# Adafruit_Ultimate_GPS_USB-C.net
KiCad netlist of a schematic drawn in EAGLE
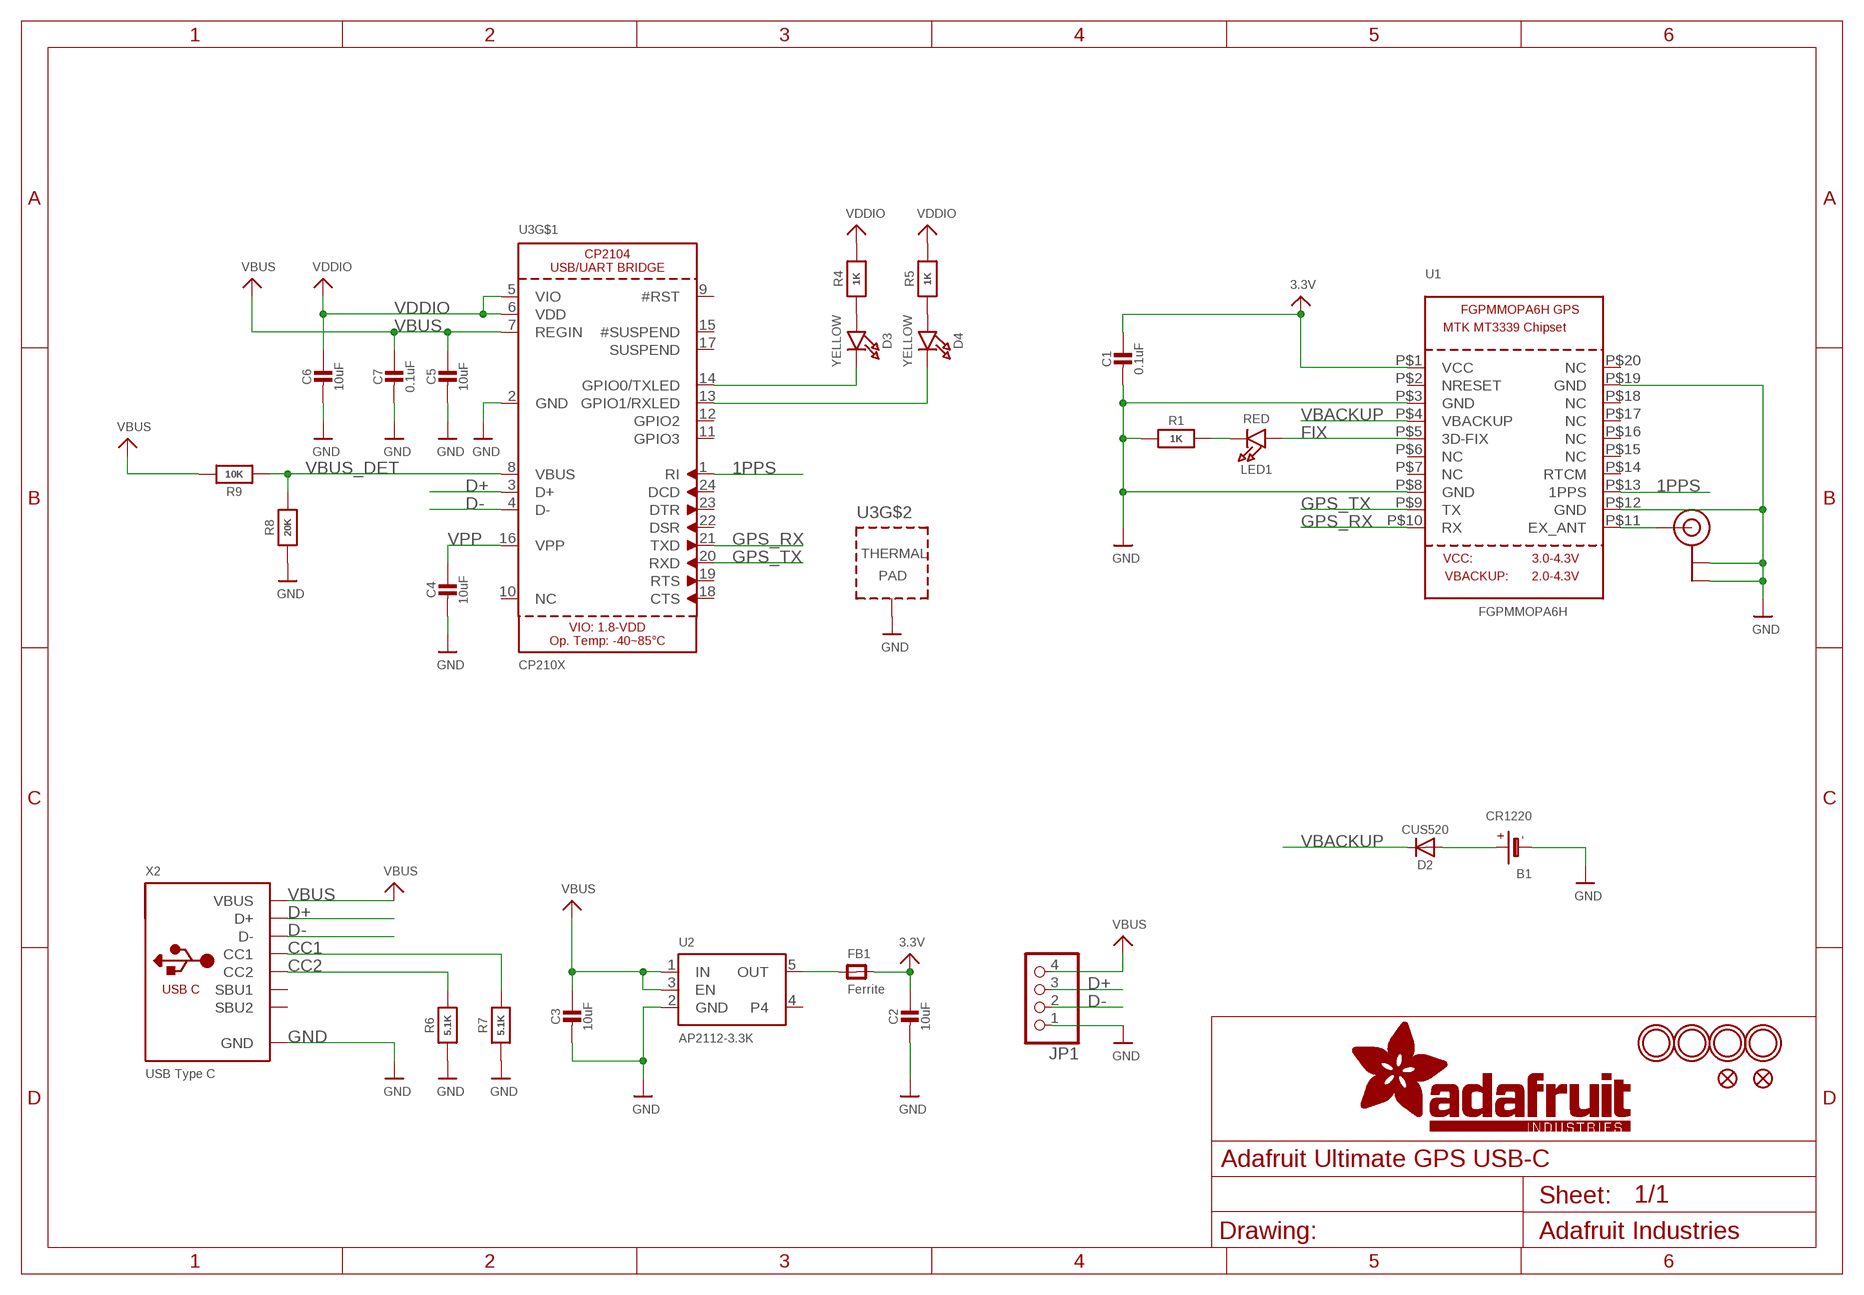
[diagram p0: schematic, sheet 1]

(export (version "E")
  (design (tool "Eeschema 10.0.6"))
  (components
    (comp (ref "B1")
      (value "CR1220")
      (footprint "eagle-import:CR1220")
      (libsource (lib "eagle-import") (part "BATTERYCR1220_SMT"))
    )
    (comp (ref "C1")
      (value "0.1uF")
      (footprint "eagle-import:0603-NO")
      (libsource (lib "eagle-import") (part "CAP_CERAMIC0603_NO"))
    )
    (comp (ref "C2")
      (value "10uF")
      (footprint "eagle-import:0805-NO")
      (libsource (lib "eagle-import") (part "CAP_CERAMIC0805-NOOUTLINE"))
    )
    (comp (ref "C3")
      (value "10uF")
      (footprint "eagle-import:0805-NO")
      (libsource (lib "eagle-import") (part "CAP_CERAMIC0805-NOOUTLINE"))
    )
    (comp (ref "C4")
      (value "10uF")
      (footprint "eagle-import:0805-NO")
      (libsource (lib "eagle-import") (part "CAP_CERAMIC0805-NOOUTLINE"))
    )
    (comp (ref "C5")
      (value "10uF")
      (footprint "eagle-import:0805-NO")
      (libsource (lib "eagle-import") (part "CAP_CERAMIC0805-NOOUTLINE"))
    )
    (comp (ref "C6")
      (value "10uF")
      (footprint "eagle-import:0805-NO")
      (libsource (lib "eagle-import") (part "CAP_CERAMIC0805-NOOUTLINE"))
    )
    (comp (ref "C7")
      (value "0.1uF")
      (footprint "eagle-import:0603-NO")
      (libsource (lib "eagle-import") (part "CAP_CERAMIC0603_NO"))
    )
    (comp (ref "D2")
      (value "CUS520")
      (footprint "eagle-import:SOD-323")
      (libsource (lib "eagle-import") (part "DIODESOD-323"))
    )
    (comp (ref "D3")
      (value "YELLOW")
      (footprint "eagle-import:CHIPLED_0805_NOOUTLINE")
      (libsource (lib "eagle-import") (part "LED0805_NOOUTLINE"))
    )
    (comp (ref "D4")
      (value "YELLOW")
      (footprint "eagle-import:CHIPLED_0805_NOOUTLINE")
      (libsource (lib "eagle-import") (part "LED0805_NOOUTLINE"))
    )
    (comp (ref "FB1")
      (value "Ferrite")
      (footprint "eagle-import:0805-NO")
      (libsource (lib "eagle-import") (part "FERRITE-0805NO"))
    )
    (comp (ref "FID1")
      (value "FIDUCIAL_1MM")
      (footprint "eagle-import:FIDUCIAL_1MM")
      (libsource (lib "eagle-import") (part "FIDUCIAL_1MM"))
    )
    (comp (ref "FID2")
      (value "FIDUCIAL_1MM")
      (footprint "eagle-import:FIDUCIAL_1MM")
      (libsource (lib "eagle-import") (part "FIDUCIAL_1MM"))
    )
    (comp (ref "JP1")
      (value "HEADER-1X4ROUND")
      (footprint "eagle-import:1X04_ROUND")
      (libsource (lib "eagle-import") (part "HEADER-1X4ROUND"))
    )
    (comp (ref "LED1")
      (value "RED")
      (footprint "eagle-import:CHIPLED_0805_NOOUTLINE")
      (libsource (lib "eagle-import") (part "LED0805_NOOUTLINE"))
    )
    (comp (ref "R1")
      (value "1K")
      (footprint "eagle-import:0603-NO")
      (libsource (lib "eagle-import") (part "RESISTOR_0603_NOOUT"))
    )
    (comp (ref "R4")
      (value "1K")
      (footprint "eagle-import:0603-NO")
      (libsource (lib "eagle-import") (part "RESISTOR_0603_NOOUT"))
    )
    (comp (ref "R5")
      (value "1K")
      (footprint "eagle-import:0603-NO")
      (libsource (lib "eagle-import") (part "RESISTOR_0603_NOOUT"))
    )
    (comp (ref "R6")
      (value "5.1K")
      (footprint "eagle-import:0603-NO")
      (libsource (lib "eagle-import") (part "RESISTOR_0603_NOOUT"))
    )
    (comp (ref "R7")
      (value "5.1K")
      (footprint "eagle-import:0603-NO")
      (libsource (lib "eagle-import") (part "RESISTOR_0603_NOOUT"))
    )
    (comp (ref "R8")
      (value "20K")
      (footprint "eagle-import:0603-NO")
      (libsource (lib "eagle-import") (part "RESISTOR_0603_NOOUT"))
    )
    (comp (ref "R9")
      (value "10K")
      (footprint "eagle-import:0603-NO")
      (libsource (lib "eagle-import") (part "RESISTOR_0603_NOOUT"))
    )
    (comp (ref "U$8")
      (value "MOUNTINGHOLE2.5")
      (footprint "eagle-import:MOUNTINGHOLE_2.5_PLATED")
      (libsource (lib "eagle-import") (part "MOUNTINGHOLE2.5"))
    )
    (comp (ref "U$9")
      (value "MOUNTINGHOLE2.5")
      (footprint "eagle-import:MOUNTINGHOLE_2.5_PLATED")
      (libsource (lib "eagle-import") (part "MOUNTINGHOLE2.5"))
    )
    (comp (ref "U$20")
      (value "U.FL")
      (footprint "eagle-import:U.FL")
      (libsource (lib "eagle-import") (part "U.FL"))
    )
    (comp (ref "U$35")
      (value "MOUNTINGHOLE2.5")
      (footprint "eagle-import:MOUNTINGHOLE_2.5_PLATED")
      (libsource (lib "eagle-import") (part "MOUNTINGHOLE2.5"))
    )
    (comp (ref "U$36")
      (value "MOUNTINGHOLE2.5")
      (footprint "eagle-import:MOUNTINGHOLE_2.5_PLATED")
      (libsource (lib "eagle-import") (part "MOUNTINGHOLE2.5"))
    )
    (comp (ref "U1")
      (value "FGPMMOPA6H")
      (footprint "eagle-import:FGPMMOPA6H")
      (libsource (lib "eagle-import") (part "GPS_FGPMMOPA6H"))
    )
    (comp (ref "U2")
      (value "AP2112-3.3K")
      (footprint "eagle-import:SOT23-5")
      (libsource (lib "eagle-import") (part "VREG_SOT23-5"))
    )
    (comp (ref "U3")
      (value "CP210X")
      (footprint "eagle-import:QFN24_4MM_SMSC")
      (libsource (lib "eagle-import") (part "CP2104"))
    )
    (comp (ref "X2")
      (value "USB Type C")
      (footprint "eagle-import:USB_C_CUSB31-CFM2AX-01-X")
      (libsource (lib "eagle-import") (part "USB_C"))
    )
  )
  (nets
    (net (code "1") (name "/1PPS") (class "Default")
      (node (ref "U1") (pin "P$13") (pinfunction "1PPS_P$13") (pintype "bidirectional"))
      (node (ref "U3") (pin "1") (pinfunction "RI_1") (pintype "input"))
    )
    (net (code "2") (name "/CC1") (class "Default")
      (node (ref "R7") (pin "2") (pinfunction "2_2") (pintype "passive"))
      (node (ref "X2") (pin "A5") (pinfunction "CC1_A5") (pintype "bidirectional"))
    )
    (net (code "3") (name "/CC2") (class "Default")
      (node (ref "R6") (pin "2") (pinfunction "2_2") (pintype "passive"))
      (node (ref "X2") (pin "B5") (pinfunction "CC2_B5") (pintype "bidirectional"))
    )
    (net (code "4") (name "/D+") (class "Default")
      (node (ref "JP1") (pin "3") (pinfunction "3_3") (pintype "passive"))
      (node (ref "U3") (pin "3") (pinfunction "D+_3") (pintype "bidirectional"))
      (node (ref "X2") (pin "A6") (pinfunction "D+_A6") (pintype "bidirectional"))
      (node (ref "X2") (pin "B6") (pinfunction "D+_B6") (pintype "bidirectional"))
    )
    (net (code "5") (name "/D-") (class "Default")
      (node (ref "JP1") (pin "2") (pinfunction "2_2") (pintype "passive"))
      (node (ref "U3") (pin "4") (pinfunction "D-_4") (pintype "bidirectional"))
      (node (ref "X2") (pin "A7") (pinfunction "D-_A7") (pintype "bidirectional"))
      (node (ref "X2") (pin "B7") (pinfunction "D-_B7") (pintype "bidirectional"))
    )
    (net (code "6") (name "/FIX") (class "Default")
      (node (ref "LED1") (pin "A") (pinfunction "A_A") (pintype "passive"))
      (node (ref "U1") (pin "P$5") (pinfunction "3D-FIX_P$5") (pintype "bidirectional"))
    )
    (net (code "7") (name "/GPS_RX") (class "Default")
      (node (ref "U1") (pin "P$10") (pinfunction "RX_P$10") (pintype "bidirectional"))
      (node (ref "U3") (pin "21") (pinfunction "TXD_21") (pintype "output"))
    )
    (net (code "8") (name "/GPS_TX") (class "Default")
      (node (ref "U1") (pin "P$9") (pinfunction "TX_P$9") (pintype "bidirectional"))
      (node (ref "U3") (pin "20") (pinfunction "RXD_20") (pintype "input"))
    )
    (net (code "9") (name "/VBACKUP") (class "Default")
      (node (ref "D2") (pin "C") (pinfunction "C_C") (pintype "passive"))
      (node (ref "U1") (pin "P$4") (pinfunction "VBACKUP_P$4") (pintype "bidirectional"))
    )
    (net (code "10") (name "/VBUS_DET") (class "Default")
      (node (ref "R8") (pin "2") (pinfunction "2_2") (pintype "passive"))
      (node (ref "R9") (pin "1") (pinfunction "1_1") (pintype "passive"))
      (node (ref "U3") (pin "8") (pinfunction "VBUS_8") (pintype "power_in"))
    )
    (net (code "11") (name "/VPP") (class "Default")
      (node (ref "C4") (pin "1") (pinfunction "1_1") (pintype "passive"))
      (node (ref "U3") (pin "16") (pinfunction "VPP_16") (pintype "bidirectional"))
    )
    (net (code "12") (name "3.3V") (class "Default")
      (node (ref "C1") (pin "1") (pinfunction "1_1") (pintype "passive"))
      (node (ref "C2") (pin "1") (pinfunction "1_1") (pintype "passive"))
      (node (ref "FB1") (pin "2") (pinfunction "P$2_2") (pintype "passive"))
      (node (ref "U1") (pin "P$1") (pinfunction "VCC_P$1") (pintype "bidirectional"))
    )
    (net (code "13") (name "GND") (class "Default")
      (node (ref "B1") (pin "-") (pinfunction "-_-") (pintype "passive"))
      (node (ref "C1") (pin "2") (pinfunction "2_2") (pintype "passive"))
      (node (ref "C2") (pin "2") (pinfunction "2_2") (pintype "passive"))
      (node (ref "C3") (pin "2") (pinfunction "2_2") (pintype "passive"))
      (node (ref "C4") (pin "2") (pinfunction "2_2") (pintype "passive"))
      (node (ref "C5") (pin "2") (pinfunction "2_2") (pintype "passive"))
      (node (ref "C6") (pin "2") (pinfunction "2_2") (pintype "passive"))
      (node (ref "C7") (pin "2") (pinfunction "2_2") (pintype "passive"))
      (node (ref "JP1") (pin "1") (pinfunction "1_1") (pintype "passive"))
      (node (ref "R1") (pin "1") (pinfunction "1_1") (pintype "passive"))
      (node (ref "R6") (pin "1") (pinfunction "1_1") (pintype "passive"))
      (node (ref "R7") (pin "1") (pinfunction "1_1") (pintype "passive"))
      (node (ref "R8") (pin "1") (pinfunction "1_1") (pintype "passive"))
      (node (ref "U$20") (pin "P$1") (pinfunction "GND_P$1") (pintype "bidirectional"))
      (node (ref "U$20") (pin "P$2") (pinfunction "GND_P$2") (pintype "bidirectional"))
      (node (ref "U1") (pin "P$12") (pinfunction "GND_P$12") (pintype "bidirectional"))
      (node (ref "U1") (pin "P$19") (pinfunction "GND_P$19") (pintype "bidirectional"))
      (node (ref "U1") (pin "P$3") (pinfunction "GND_P$3") (pintype "bidirectional"))
      (node (ref "U1") (pin "P$8") (pinfunction "GND_P$8") (pintype "bidirectional"))
      (node (ref "U2") (pin "2") (pinfunction "GND_2") (pintype "power_in"))
      (node (ref "U3") (pin "2") (pinfunction "GND_2") (pintype "power_in"))
      (node (ref "U3") (pin "THERM") (pinfunction "TP_THERM") (pintype "power_in"))
      (node (ref "X2") (pin "A1B12") (pinfunction "GND_A1B12") (pintype "power_in"))
      (node (ref "X2") (pin "B1A12") (pinfunction "GND_B1A12") (pintype "power_in"))
    )
    (net (code "14") (name "Net-(B1-+-Pad+$1)") (class "Default")
      (node (ref "B1") (pin "+$1") (pinfunction "+_+$1") (pintype "passive"))
      (node (ref "B1") (pin "+$2") (pinfunction "+_+$2") (pintype "passive"))
      (node (ref "D2") (pin "A") (pinfunction "A_A") (pintype "passive"))
    )
    (net (code "15") (name "Net-(D3-PadA)") (class "Default")
      (node (ref "D3") (pin "A") (pinfunction "A_A") (pintype "passive"))
      (node (ref "R4") (pin "1") (pinfunction "1_1") (pintype "passive"))
    )
    (net (code "16") (name "Net-(D4-PadA)") (class "Default")
      (node (ref "D4") (pin "A") (pinfunction "A_A") (pintype "passive"))
      (node (ref "R5") (pin "1") (pinfunction "1_1") (pintype "passive"))
    )
    (net (code "17") (name "Net-(FB1-P$1)") (class "Default")
      (node (ref "FB1") (pin "1") (pinfunction "P$1_1") (pintype "passive"))
      (node (ref "U2") (pin "5") (pinfunction "OUT_5") (pintype "power_in"))
    )
    (net (code "18") (name "Net-(LED1-PadC)") (class "Default")
      (node (ref "LED1") (pin "C") (pinfunction "C_C") (pintype "passive"))
      (node (ref "R1") (pin "2") (pinfunction "2_2") (pintype "passive"))
    )
    (net (code "19") (name "Net-(U$20-SIGNAL)") (class "Default")
      (node (ref "U$20") (pin "P$3") (pinfunction "SIGNAL_P$3") (pintype "bidirectional"))
      (node (ref "U1") (pin "P$11") (pinfunction "EX_ANT_P$11") (pintype "bidirectional"))
    )
    (net (code "20") (name "Net-(U3A-GPIO0{slash}TXLED)") (class "Default")
      (node (ref "D3") (pin "C") (pinfunction "C_C") (pintype "passive"))
      (node (ref "U3") (pin "14") (pinfunction "GPIO0/TXLED_14") (pintype "bidirectional"))
    )
    (net (code "21") (name "Net-(U3A-GPIO1{slash}RXLED)") (class "Default")
      (node (ref "D4") (pin "C") (pinfunction "C_C") (pintype "passive"))
      (node (ref "U3") (pin "13") (pinfunction "GPIO1/RXLED_13") (pintype "bidirectional"))
    )
    (net (code "22") (name "VBUS") (class "Default")
      (node (ref "C3") (pin "1") (pinfunction "1_1") (pintype "passive"))
      (node (ref "C5") (pin "1") (pinfunction "1_1") (pintype "passive"))
      (node (ref "C7") (pin "1") (pinfunction "1_1") (pintype "passive"))
      (node (ref "JP1") (pin "4") (pinfunction "4_4") (pintype "passive"))
      (node (ref "R9") (pin "2") (pinfunction "2_2") (pintype "passive"))
      (node (ref "U2") (pin "1") (pinfunction "IN_1") (pintype "power_in"))
      (node (ref "U2") (pin "3") (pinfunction "EN_3") (pintype "input"))
      (node (ref "U3") (pin "7") (pinfunction "REGIN_7") (pintype "power_in"))
      (node (ref "X2") (pin "A4B9") (pinfunction "VBUS_A4B9") (pintype "power_in"))
      (node (ref "X2") (pin "B4A9") (pinfunction "VBUS_B4A9") (pintype "power_in"))
    )
    (net (code "23") (name "VDDIO") (class "Default")
      (node (ref "C6") (pin "1") (pinfunction "1_1") (pintype "passive"))
      (node (ref "R4") (pin "2") (pinfunction "2_2") (pintype "passive"))
      (node (ref "R5") (pin "2") (pinfunction "2_2") (pintype "passive"))
      (node (ref "U3") (pin "5") (pinfunction "VIO_5") (pintype "power_in"))
      (node (ref "U3") (pin "6") (pinfunction "VDD_6") (pintype "power_in"))
    )
    (net (code "24") (name "unconnected-(U1-NC-PadP$6)") (class "Default")
      (node (ref "U1") (pin "P$6") (pinfunction "NC_P$6") (pintype "bidirectional"))
    )
    (net (code "25") (name "unconnected-(U1-NC-PadP$7)") (class "Default")
      (node (ref "U1") (pin "P$7") (pinfunction "NC_P$7") (pintype "bidirectional"))
    )
    (net (code "26") (name "unconnected-(U1-NC-PadP$15)") (class "Default")
      (node (ref "U1") (pin "P$15") (pinfunction "NC_P$15") (pintype "bidirectional"))
    )
    (net (code "27") (name "unconnected-(U1-NC-PadP$16)") (class "Default")
      (node (ref "U1") (pin "P$16") (pinfunction "NC_P$16") (pintype "bidirectional"))
    )
    (net (code "28") (name "unconnected-(U1-NC-PadP$17)") (class "Default")
      (node (ref "U1") (pin "P$17") (pinfunction "NC_P$17") (pintype "bidirectional"))
    )
    (net (code "29") (name "unconnected-(U1-NC-PadP$18)") (class "Default")
      (node (ref "U1") (pin "P$18") (pinfunction "NC_P$18") (pintype "bidirectional"))
    )
    (net (code "30") (name "unconnected-(U1-NC-PadP$20)") (class "Default")
      (node (ref "U1") (pin "P$20") (pinfunction "NC_P$20") (pintype "bidirectional"))
    )
    (net (code "31") (name "unconnected-(U1-NRESET-PadP$2)") (class "Default")
      (node (ref "U1") (pin "P$2") (pinfunction "NRESET_P$2") (pintype "bidirectional"))
    )
    (net (code "32") (name "unconnected-(U1-RTCM-PadP$14)") (class "Default")
      (node (ref "U1") (pin "P$14") (pinfunction "RTCM_P$14") (pintype "bidirectional"))
    )
    (net (code "33") (name "unconnected-(U2-P4-Pad4)") (class "Default")
      (node (ref "U2") (pin "4") (pinfunction "P4_4") (pintype "bidirectional"))
    )
    (net (code "34") (name "unconnected-(U3A-#RST-Pad9)") (class "Default")
      (node (ref "U3") (pin "9") (pinfunction "#RST_9") (pintype "bidirectional"))
    )
    (net (code "35") (name "unconnected-(U3A-#SUSPEND-Pad15)") (class "Default")
      (node (ref "U3") (pin "15") (pinfunction "#SUSPEND_15") (pintype "output"))
    )
    (net (code "36") (name "unconnected-(U3A-CTS-Pad18)") (class "Default")
      (node (ref "U3") (pin "18") (pinfunction "CTS_18") (pintype "input"))
    )
    (net (code "37") (name "unconnected-(U3A-DCD-Pad24)") (class "Default")
      (node (ref "U3") (pin "24") (pinfunction "DCD_24") (pintype "input"))
    )
    (net (code "38") (name "unconnected-(U3A-DSR-Pad22)") (class "Default")
      (node (ref "U3") (pin "22") (pinfunction "DSR_22") (pintype "input"))
    )
    (net (code "39") (name "unconnected-(U3A-DTR-Pad23)") (class "Default")
      (node (ref "U3") (pin "23") (pinfunction "DTR_23") (pintype "output"))
    )
    (net (code "40") (name "unconnected-(U3A-GPIO2-Pad12)") (class "Default")
      (node (ref "U3") (pin "12") (pinfunction "GPIO2_12") (pintype "bidirectional"))
    )
    (net (code "41") (name "unconnected-(U3A-GPIO3-Pad11)") (class "Default")
      (node (ref "U3") (pin "11") (pinfunction "GPIO3_11") (pintype "bidirectional"))
    )
    (net (code "42") (name "unconnected-(U3A-NC-Pad10)") (class "Default")
      (node (ref "U3") (pin "10") (pinfunction "NC_10") (pintype "no_connect"))
    )
    (net (code "43") (name "unconnected-(U3A-RTS-Pad19)") (class "Default")
      (node (ref "U3") (pin "19") (pinfunction "RTS_19") (pintype "output"))
    )
    (net (code "44") (name "unconnected-(U3A-SUSPEND-Pad17)") (class "Default")
      (node (ref "U3") (pin "17") (pinfunction "SUSPEND_17") (pintype "output"))
    )
    (net (code "45") (name "unconnected-(X2-SBU1-PadA8)") (class "Default")
      (node (ref "X2") (pin "A8") (pinfunction "SBU1_A8") (pintype "bidirectional"))
    )
    (net (code "46") (name "unconnected-(X2-SBU2-PadB8)") (class "Default")
      (node (ref "X2") (pin "B8") (pinfunction "SBU2_B8") (pintype "bidirectional"))
    )
  )
)
